# 1_-multipass.net
KiCad netlist of a schematic drawn in Altium Designer
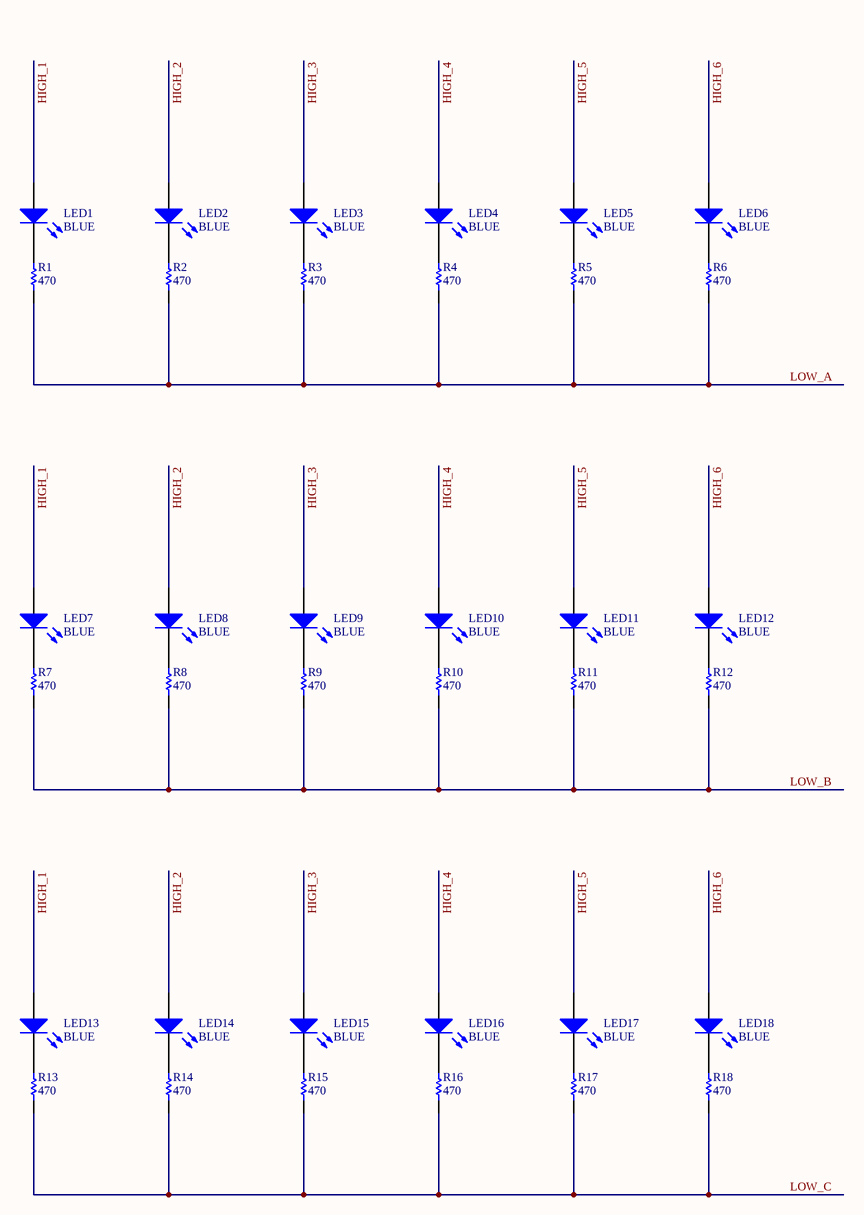
[diagram p0: [1]-multipass.SchDoc]

(export (version "E")
  (design (tool "Eeschema 10.0.6"))
  (components
    (comp (ref "LED1")
      (value "BLUE")
      (footprint "0603_A")
      (description "SMD mono-color Chip LED, WL-SMCW, Green")
      (fields (field (name "MANUFACTURER") "Wuerth Elektronik") (field (name "MPN") "150060GS75000"))
      (libsource (lib "Altium Content Vault") (part "CMP-1426-00002-1"))
    )
    (comp (ref "LED2")
      (value "BLUE")
      (footprint "0603_A")
      (description "SMD mono-color Chip LED, WL-SMCW, Green")
      (fields (field (name "MANUFACTURER") "Wuerth Elektronik") (field (name "MPN") "150060GS75000"))
      (libsource (lib "Altium Content Vault") (part "CMP-1426-00002-1"))
    )
    (comp (ref "LED3")
      (value "BLUE")
      (footprint "0603_A")
      (description "SMD mono-color Chip LED, WL-SMCW, Green")
      (fields (field (name "MANUFACTURER") "Wuerth Elektronik") (field (name "MPN") "150060GS75000"))
      (libsource (lib "Altium Content Vault") (part "CMP-1426-00002-1"))
    )
    (comp (ref "LED4")
      (value "BLUE")
      (footprint "0603_A")
      (description "SMD mono-color Chip LED, WL-SMCW, Green")
      (fields (field (name "MANUFACTURER") "Wuerth Elektronik") (field (name "MPN") "150060GS75000"))
      (libsource (lib "Altium Content Vault") (part "CMP-1426-00002-1"))
    )
    (comp (ref "LED5")
      (value "BLUE")
      (footprint "0603_A")
      (description "SMD mono-color Chip LED, WL-SMCW, Green")
      (fields (field (name "MANUFACTURER") "Wuerth Elektronik") (field (name "MPN") "150060GS75000"))
      (libsource (lib "Altium Content Vault") (part "CMP-1426-00002-1"))
    )
    (comp (ref "LED6")
      (value "BLUE")
      (footprint "0603_A")
      (description "SMD mono-color Chip LED, WL-SMCW, Green")
      (fields (field (name "MANUFACTURER") "Wuerth Elektronik") (field (name "MPN") "150060GS75000"))
      (libsource (lib "Altium Content Vault") (part "CMP-1426-00002-1"))
    )
    (comp (ref "LED7")
      (value "BLUE")
      (footprint "0603_A")
      (description "SMD mono-color Chip LED, WL-SMCW, Green")
      (fields (field (name "MANUFACTURER") "Wuerth Elektronik") (field (name "MPN") "150060GS75000"))
      (libsource (lib "Altium Content Vault") (part "CMP-1426-00002-1"))
    )
    (comp (ref "LED8")
      (value "BLUE")
      (footprint "0603_A")
      (description "SMD mono-color Chip LED, WL-SMCW, Green")
      (fields (field (name "MANUFACTURER") "Wuerth Elektronik") (field (name "MPN") "150060GS75000"))
      (libsource (lib "Altium Content Vault") (part "CMP-1426-00002-1"))
    )
    (comp (ref "LED9")
      (value "BLUE")
      (footprint "0603_A")
      (description "SMD mono-color Chip LED, WL-SMCW, Green")
      (fields (field (name "MANUFACTURER") "Wuerth Elektronik") (field (name "MPN") "150060GS75000"))
      (libsource (lib "Altium Content Vault") (part "CMP-1426-00002-1"))
    )
    (comp (ref "LED10")
      (value "BLUE")
      (footprint "0603_A")
      (description "SMD mono-color Chip LED, WL-SMCW, Green")
      (fields (field (name "MANUFACTURER") "Wuerth Elektronik") (field (name "MPN") "150060GS75000"))
      (libsource (lib "Altium Content Vault") (part "CMP-1426-00002-1"))
    )
    (comp (ref "LED11")
      (value "BLUE")
      (footprint "0603_A")
      (description "SMD mono-color Chip LED, WL-SMCW, Green")
      (fields (field (name "MANUFACTURER") "Wuerth Elektronik") (field (name "MPN") "150060GS75000"))
      (libsource (lib "Altium Content Vault") (part "CMP-1426-00002-1"))
    )
    (comp (ref "LED12")
      (value "BLUE")
      (footprint "0603_A")
      (description "SMD mono-color Chip LED, WL-SMCW, Green")
      (fields (field (name "MANUFACTURER") "Wuerth Elektronik") (field (name "MPN") "150060GS75000"))
      (libsource (lib "Altium Content Vault") (part "CMP-1426-00002-1"))
    )
    (comp (ref "LED13")
      (value "BLUE")
      (footprint "0603_A")
      (description "SMD mono-color Chip LED, WL-SMCW, Green")
      (fields (field (name "MANUFACTURER") "Wuerth Elektronik") (field (name "MPN") "150060GS75000"))
      (libsource (lib "Altium Content Vault") (part "CMP-1426-00002-1"))
    )
    (comp (ref "LED14")
      (value "BLUE")
      (footprint "0603_A")
      (description "SMD mono-color Chip LED, WL-SMCW, Green")
      (fields (field (name "MANUFACTURER") "Wuerth Elektronik") (field (name "MPN") "150060GS75000"))
      (libsource (lib "Altium Content Vault") (part "CMP-1426-00002-1"))
    )
    (comp (ref "LED15")
      (value "BLUE")
      (footprint "0603_A")
      (description "SMD mono-color Chip LED, WL-SMCW, Green")
      (fields (field (name "MANUFACTURER") "Wuerth Elektronik") (field (name "MPN") "150060GS75000"))
      (libsource (lib "Altium Content Vault") (part "CMP-1426-00002-1"))
    )
    (comp (ref "LED16")
      (value "BLUE")
      (footprint "0603_A")
      (description "SMD mono-color Chip LED, WL-SMCW, Green")
      (fields (field (name "MANUFACTURER") "Wuerth Elektronik") (field (name "MPN") "150060GS75000"))
      (libsource (lib "Altium Content Vault") (part "CMP-1426-00002-1"))
    )
    (comp (ref "LED17")
      (value "BLUE")
      (footprint "0603_A")
      (description "SMD mono-color Chip LED, WL-SMCW, Green")
      (fields (field (name "MANUFACTURER") "Wuerth Elektronik") (field (name "MPN") "150060GS75000"))
      (libsource (lib "Altium Content Vault") (part "CMP-1426-00002-1"))
    )
    (comp (ref "LED18")
      (value "BLUE")
      (footprint "0603_A")
      (description "SMD mono-color Chip LED, WL-SMCW, Green")
      (fields (field (name "MANUFACTURER") "Wuerth Elektronik") (field (name "MPN") "150060GS75000"))
      (libsource (lib "Altium Content Vault") (part "CMP-1426-00002-1"))
    )
    (comp (ref "R1")
      (value "470")
      (footprint "RESC0402(1005)_L")
      (description "10K 0.063W 1% 0402 (1005 Metric)  SMD")
      (fields (field (name "MPN") "RC0402JR-07470RL") (field (name "MANUFACTURER") "Yageo"))
      (libsource (lib "Altium Content Vault") (part "RES"))
    )
    (comp (ref "R2")
      (value "470")
      (footprint "RESC0402(1005)_L")
      (description "10K 0.063W 1% 0402 (1005 Metric)  SMD")
      (fields (field (name "MPN") "RC0402JR-07470RL") (field (name "MANUFACTURER") "Yageo"))
      (libsource (lib "Altium Content Vault") (part "RES"))
    )
    (comp (ref "R3")
      (value "470")
      (footprint "RESC0402(1005)_L")
      (description "10K 0.063W 1% 0402 (1005 Metric)  SMD")
      (fields (field (name "MPN") "RC0402JR-07470RL") (field (name "MANUFACTURER") "Yageo"))
      (libsource (lib "Altium Content Vault") (part "RES"))
    )
    (comp (ref "R4")
      (value "470")
      (footprint "RESC0402(1005)_L")
      (description "10K 0.063W 1% 0402 (1005 Metric)  SMD")
      (fields (field (name "MPN") "RC0402JR-07470RL") (field (name "MANUFACTURER") "Yageo"))
      (libsource (lib "Altium Content Vault") (part "RES"))
    )
    (comp (ref "R5")
      (value "470")
      (footprint "RESC0402(1005)_L")
      (description "10K 0.063W 1% 0402 (1005 Metric)  SMD")
      (fields (field (name "MPN") "RC0402JR-07470RL") (field (name "MANUFACTURER") "Yageo"))
      (libsource (lib "Altium Content Vault") (part "RES"))
    )
    (comp (ref "R6")
      (value "470")
      (footprint "RESC0402(1005)_L")
      (description "10K 0.063W 1% 0402 (1005 Metric)  SMD")
      (fields (field (name "MPN") "RC0402JR-07470RL") (field (name "MANUFACTURER") "Yageo"))
      (libsource (lib "Altium Content Vault") (part "RES"))
    )
    (comp (ref "R7")
      (value "470")
      (footprint "RESC0402(1005)_L")
      (description "10K 0.063W 1% 0402 (1005 Metric)  SMD")
      (fields (field (name "MPN") "RC0402JR-07470RL") (field (name "MANUFACTURER") "Yageo"))
      (libsource (lib "Altium Content Vault") (part "RES"))
    )
    (comp (ref "R8")
      (value "470")
      (footprint "RESC0402(1005)_L")
      (description "10K 0.063W 1% 0402 (1005 Metric)  SMD")
      (fields (field (name "MPN") "RC0402JR-07470RL") (field (name "MANUFACTURER") "Yageo"))
      (libsource (lib "Altium Content Vault") (part "RES"))
    )
    (comp (ref "R9")
      (value "470")
      (footprint "RESC0402(1005)_L")
      (description "10K 0.063W 1% 0402 (1005 Metric)  SMD")
      (fields (field (name "MPN") "RC0402JR-07470RL") (field (name "MANUFACTURER") "Yageo"))
      (libsource (lib "Altium Content Vault") (part "RES"))
    )
    (comp (ref "R10")
      (value "470")
      (footprint "RESC0402(1005)_L")
      (description "10K 0.063W 1% 0402 (1005 Metric)  SMD")
      (fields (field (name "MPN") "RC0402JR-07470RL") (field (name "MANUFACTURER") "Yageo"))
      (libsource (lib "Altium Content Vault") (part "RES"))
    )
    (comp (ref "R11")
      (value "470")
      (footprint "RESC0402(1005)_L")
      (description "10K 0.063W 1% 0402 (1005 Metric)  SMD")
      (fields (field (name "MPN") "RC0402JR-07470RL") (field (name "MANUFACTURER") "Yageo"))
      (libsource (lib "Altium Content Vault") (part "RES"))
    )
    (comp (ref "R12")
      (value "470")
      (footprint "RESC0402(1005)_L")
      (description "10K 0.063W 1% 0402 (1005 Metric)  SMD")
      (fields (field (name "MPN") "RC0402JR-07470RL") (field (name "MANUFACTURER") "Yageo"))
      (libsource (lib "Altium Content Vault") (part "RES"))
    )
    (comp (ref "R13")
      (value "470")
      (footprint "RESC0402(1005)_L")
      (description "10K 0.063W 1% 0402 (1005 Metric)  SMD")
      (fields (field (name "MPN") "RC0402JR-07470RL") (field (name "MANUFACTURER") "Yageo"))
      (libsource (lib "Altium Content Vault") (part "RES"))
    )
    (comp (ref "R14")
      (value "470")
      (footprint "RESC0402(1005)_L")
      (description "10K 0.063W 1% 0402 (1005 Metric)  SMD")
      (fields (field (name "MPN") "RC0402JR-07470RL") (field (name "MANUFACTURER") "Yageo"))
      (libsource (lib "Altium Content Vault") (part "RES"))
    )
    (comp (ref "R15")
      (value "470")
      (footprint "RESC0402(1005)_L")
      (description "10K 0.063W 1% 0402 (1005 Metric)  SMD")
      (fields (field (name "MPN") "RC0402JR-07470RL") (field (name "MANUFACTURER") "Yageo"))
      (libsource (lib "Altium Content Vault") (part "RES"))
    )
    (comp (ref "R16")
      (value "470")
      (footprint "RESC0402(1005)_L")
      (description "10K 0.063W 1% 0402 (1005 Metric)  SMD")
      (fields (field (name "MPN") "RC0402JR-07470RL") (field (name "MANUFACTURER") "Yageo"))
      (libsource (lib "Altium Content Vault") (part "RES"))
    )
    (comp (ref "R17")
      (value "470")
      (footprint "RESC0402(1005)_L")
      (description "10K 0.063W 1% 0402 (1005 Metric)  SMD")
      (fields (field (name "MPN") "RC0402JR-07470RL") (field (name "MANUFACTURER") "Yageo"))
      (libsource (lib "Altium Content Vault") (part "RES"))
    )
    (comp (ref "R18")
      (value "470")
      (footprint "RESC0402(1005)_L")
      (description "10K 0.063W 1% 0402 (1005 Metric)  SMD")
      (fields (field (name "MPN") "RC0402JR-07470RL") (field (name "MANUFACTURER") "Yageo"))
      (libsource (lib "Altium Content Vault") (part "RES"))
    )
  )
  (nets
    (net (code "1") (name "/HIGH_1") (class "Default")
      (node (ref "LED1") (pin "2") (pinfunction "A_2") (pintype "passive"))
      (node (ref "LED13") (pin "2") (pinfunction "A_2") (pintype "passive"))
      (node (ref "LED7") (pin "2") (pinfunction "A_2") (pintype "passive"))
    )
    (net (code "2") (name "/HIGH_2") (class "Default")
      (node (ref "LED14") (pin "2") (pinfunction "A_2") (pintype "passive"))
      (node (ref "LED2") (pin "2") (pinfunction "A_2") (pintype "passive"))
      (node (ref "LED8") (pin "2") (pinfunction "A_2") (pintype "passive"))
    )
    (net (code "3") (name "/HIGH_3") (class "Default")
      (node (ref "LED15") (pin "2") (pinfunction "A_2") (pintype "passive"))
      (node (ref "LED3") (pin "2") (pinfunction "A_2") (pintype "passive"))
      (node (ref "LED9") (pin "2") (pinfunction "A_2") (pintype "passive"))
    )
    (net (code "4") (name "/HIGH_4") (class "Default")
      (node (ref "LED10") (pin "2") (pinfunction "A_2") (pintype "passive"))
      (node (ref "LED16") (pin "2") (pinfunction "A_2") (pintype "passive"))
      (node (ref "LED4") (pin "2") (pinfunction "A_2") (pintype "passive"))
    )
    (net (code "5") (name "/HIGH_5") (class "Default")
      (node (ref "LED11") (pin "2") (pinfunction "A_2") (pintype "passive"))
      (node (ref "LED17") (pin "2") (pinfunction "A_2") (pintype "passive"))
      (node (ref "LED5") (pin "2") (pinfunction "A_2") (pintype "passive"))
    )
    (net (code "6") (name "/HIGH_6") (class "Default")
      (node (ref "LED12") (pin "2") (pinfunction "A_2") (pintype "passive"))
      (node (ref "LED18") (pin "2") (pinfunction "A_2") (pintype "passive"))
      (node (ref "LED6") (pin "2") (pinfunction "A_2") (pintype "passive"))
    )
    (net (code "7") (name "/LOW_A") (class "Default")
      (node (ref "R1") (pin "1") (pinfunction "1_1") (pintype "passive"))
      (node (ref "R2") (pin "1") (pinfunction "1_1") (pintype "passive"))
      (node (ref "R3") (pin "1") (pinfunction "1_1") (pintype "passive"))
      (node (ref "R4") (pin "1") (pinfunction "1_1") (pintype "passive"))
      (node (ref "R5") (pin "1") (pinfunction "1_1") (pintype "passive"))
      (node (ref "R6") (pin "1") (pinfunction "1_1") (pintype "passive"))
    )
    (net (code "8") (name "/LOW_B") (class "Default")
      (node (ref "R10") (pin "1") (pinfunction "1_1") (pintype "passive"))
      (node (ref "R11") (pin "1") (pinfunction "1_1") (pintype "passive"))
      (node (ref "R12") (pin "1") (pinfunction "1_1") (pintype "passive"))
      (node (ref "R7") (pin "1") (pinfunction "1_1") (pintype "passive"))
      (node (ref "R8") (pin "1") (pinfunction "1_1") (pintype "passive"))
      (node (ref "R9") (pin "1") (pinfunction "1_1") (pintype "passive"))
    )
    (net (code "9") (name "/LOW_C") (class "Default")
      (node (ref "R13") (pin "1") (pinfunction "1_1") (pintype "passive"))
      (node (ref "R14") (pin "1") (pinfunction "1_1") (pintype "passive"))
      (node (ref "R15") (pin "1") (pinfunction "1_1") (pintype "passive"))
      (node (ref "R16") (pin "1") (pinfunction "1_1") (pintype "passive"))
      (node (ref "R17") (pin "1") (pinfunction "1_1") (pintype "passive"))
      (node (ref "R18") (pin "1") (pinfunction "1_1") (pintype "passive"))
    )
    (net (code "10") (name "Net-(LED1-K)") (class "Default")
      (node (ref "LED1") (pin "1") (pinfunction "K_1") (pintype "passive"))
      (node (ref "R1") (pin "2") (pinfunction "2_2") (pintype "passive"))
    )
    (net (code "11") (name "Net-(LED2-K)") (class "Default")
      (node (ref "LED2") (pin "1") (pinfunction "K_1") (pintype "passive"))
      (node (ref "R2") (pin "2") (pinfunction "2_2") (pintype "passive"))
    )
    (net (code "12") (name "Net-(LED3-K)") (class "Default")
      (node (ref "LED3") (pin "1") (pinfunction "K_1") (pintype "passive"))
      (node (ref "R3") (pin "2") (pinfunction "2_2") (pintype "passive"))
    )
    (net (code "13") (name "Net-(LED4-K)") (class "Default")
      (node (ref "LED4") (pin "1") (pinfunction "K_1") (pintype "passive"))
      (node (ref "R4") (pin "2") (pinfunction "2_2") (pintype "passive"))
    )
    (net (code "14") (name "Net-(LED5-K)") (class "Default")
      (node (ref "LED5") (pin "1") (pinfunction "K_1") (pintype "passive"))
      (node (ref "R5") (pin "2") (pinfunction "2_2") (pintype "passive"))
    )
    (net (code "15") (name "Net-(LED6-K)") (class "Default")
      (node (ref "LED6") (pin "1") (pinfunction "K_1") (pintype "passive"))
      (node (ref "R6") (pin "2") (pinfunction "2_2") (pintype "passive"))
    )
    (net (code "16") (name "Net-(LED7-K)") (class "Default")
      (node (ref "LED7") (pin "1") (pinfunction "K_1") (pintype "passive"))
      (node (ref "R7") (pin "2") (pinfunction "2_2") (pintype "passive"))
    )
    (net (code "17") (name "Net-(LED8-K)") (class "Default")
      (node (ref "LED8") (pin "1") (pinfunction "K_1") (pintype "passive"))
      (node (ref "R8") (pin "2") (pinfunction "2_2") (pintype "passive"))
    )
    (net (code "18") (name "Net-(LED9-K)") (class "Default")
      (node (ref "LED9") (pin "1") (pinfunction "K_1") (pintype "passive"))
      (node (ref "R9") (pin "2") (pinfunction "2_2") (pintype "passive"))
    )
    (net (code "19") (name "Net-(LED10-K)") (class "Default")
      (node (ref "LED10") (pin "1") (pinfunction "K_1") (pintype "passive"))
      (node (ref "R10") (pin "2") (pinfunction "2_2") (pintype "passive"))
    )
    (net (code "20") (name "Net-(LED11-K)") (class "Default")
      (node (ref "LED11") (pin "1") (pinfunction "K_1") (pintype "passive"))
      (node (ref "R11") (pin "2") (pinfunction "2_2") (pintype "passive"))
    )
    (net (code "21") (name "Net-(LED12-K)") (class "Default")
      (node (ref "LED12") (pin "1") (pinfunction "K_1") (pintype "passive"))
      (node (ref "R12") (pin "2") (pinfunction "2_2") (pintype "passive"))
    )
    (net (code "22") (name "Net-(LED13-K)") (class "Default")
      (node (ref "LED13") (pin "1") (pinfunction "K_1") (pintype "passive"))
      (node (ref "R13") (pin "2") (pinfunction "2_2") (pintype "passive"))
    )
    (net (code "23") (name "Net-(LED14-K)") (class "Default")
      (node (ref "LED14") (pin "1") (pinfunction "K_1") (pintype "passive"))
      (node (ref "R14") (pin "2") (pinfunction "2_2") (pintype "passive"))
    )
    (net (code "24") (name "Net-(LED15-K)") (class "Default")
      (node (ref "LED15") (pin "1") (pinfunction "K_1") (pintype "passive"))
      (node (ref "R15") (pin "2") (pinfunction "2_2") (pintype "passive"))
    )
    (net (code "25") (name "Net-(LED16-K)") (class "Default")
      (node (ref "LED16") (pin "1") (pinfunction "K_1") (pintype "passive"))
      (node (ref "R16") (pin "2") (pinfunction "2_2") (pintype "passive"))
    )
    (net (code "26") (name "Net-(LED17-K)") (class "Default")
      (node (ref "LED17") (pin "1") (pinfunction "K_1") (pintype "passive"))
      (node (ref "R17") (pin "2") (pinfunction "2_2") (pintype "passive"))
    )
    (net (code "27") (name "Net-(LED18-K)") (class "Default")
      (node (ref "LED18") (pin "1") (pinfunction "K_1") (pintype "passive"))
      (node (ref "R18") (pin "2") (pinfunction "2_2") (pintype "passive"))
    )
  )
)
